# Sheet1.net
KiCad netlist of a schematic drawn in Altium Designer
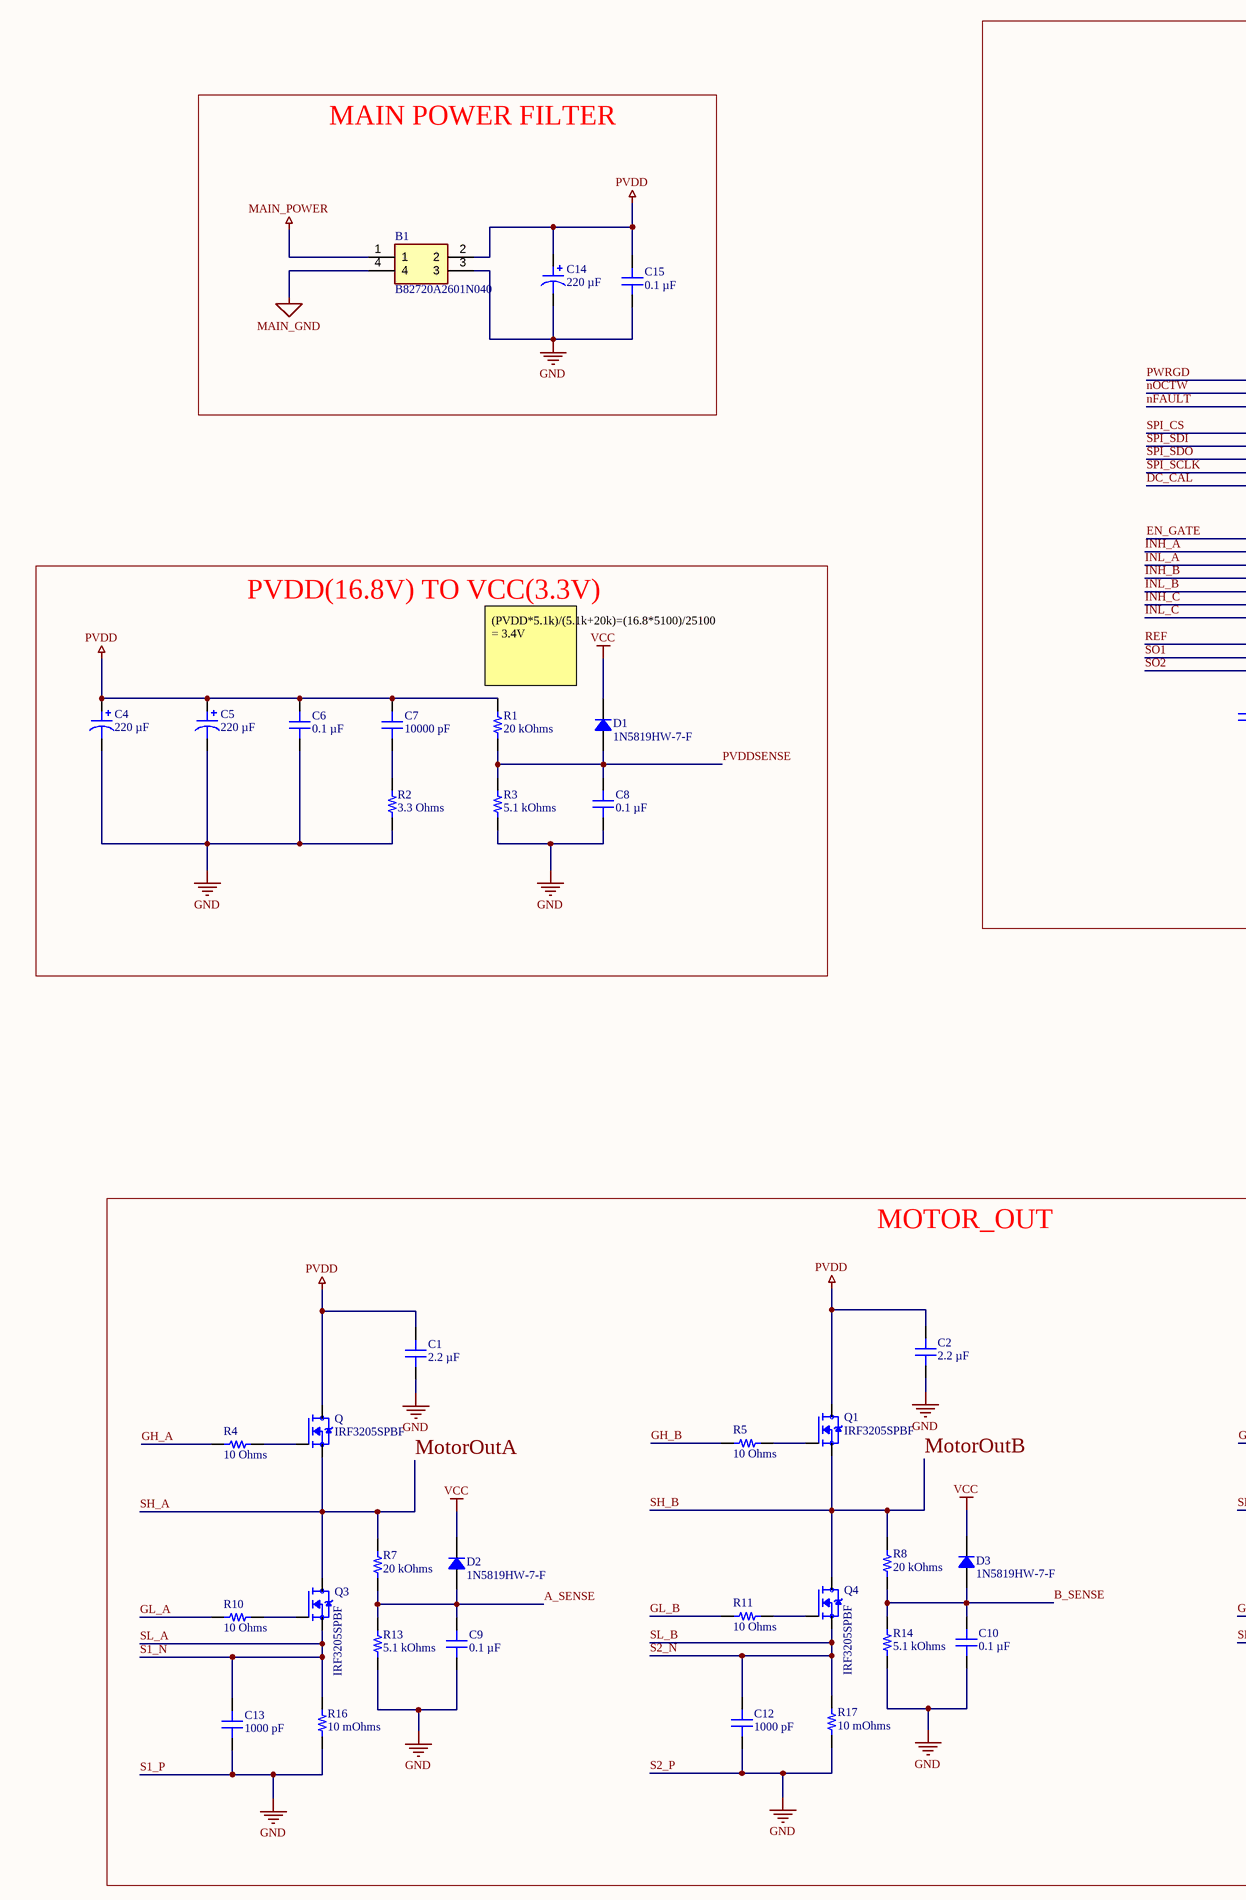
[diagram p0: Sheet1.SchDoc, left]
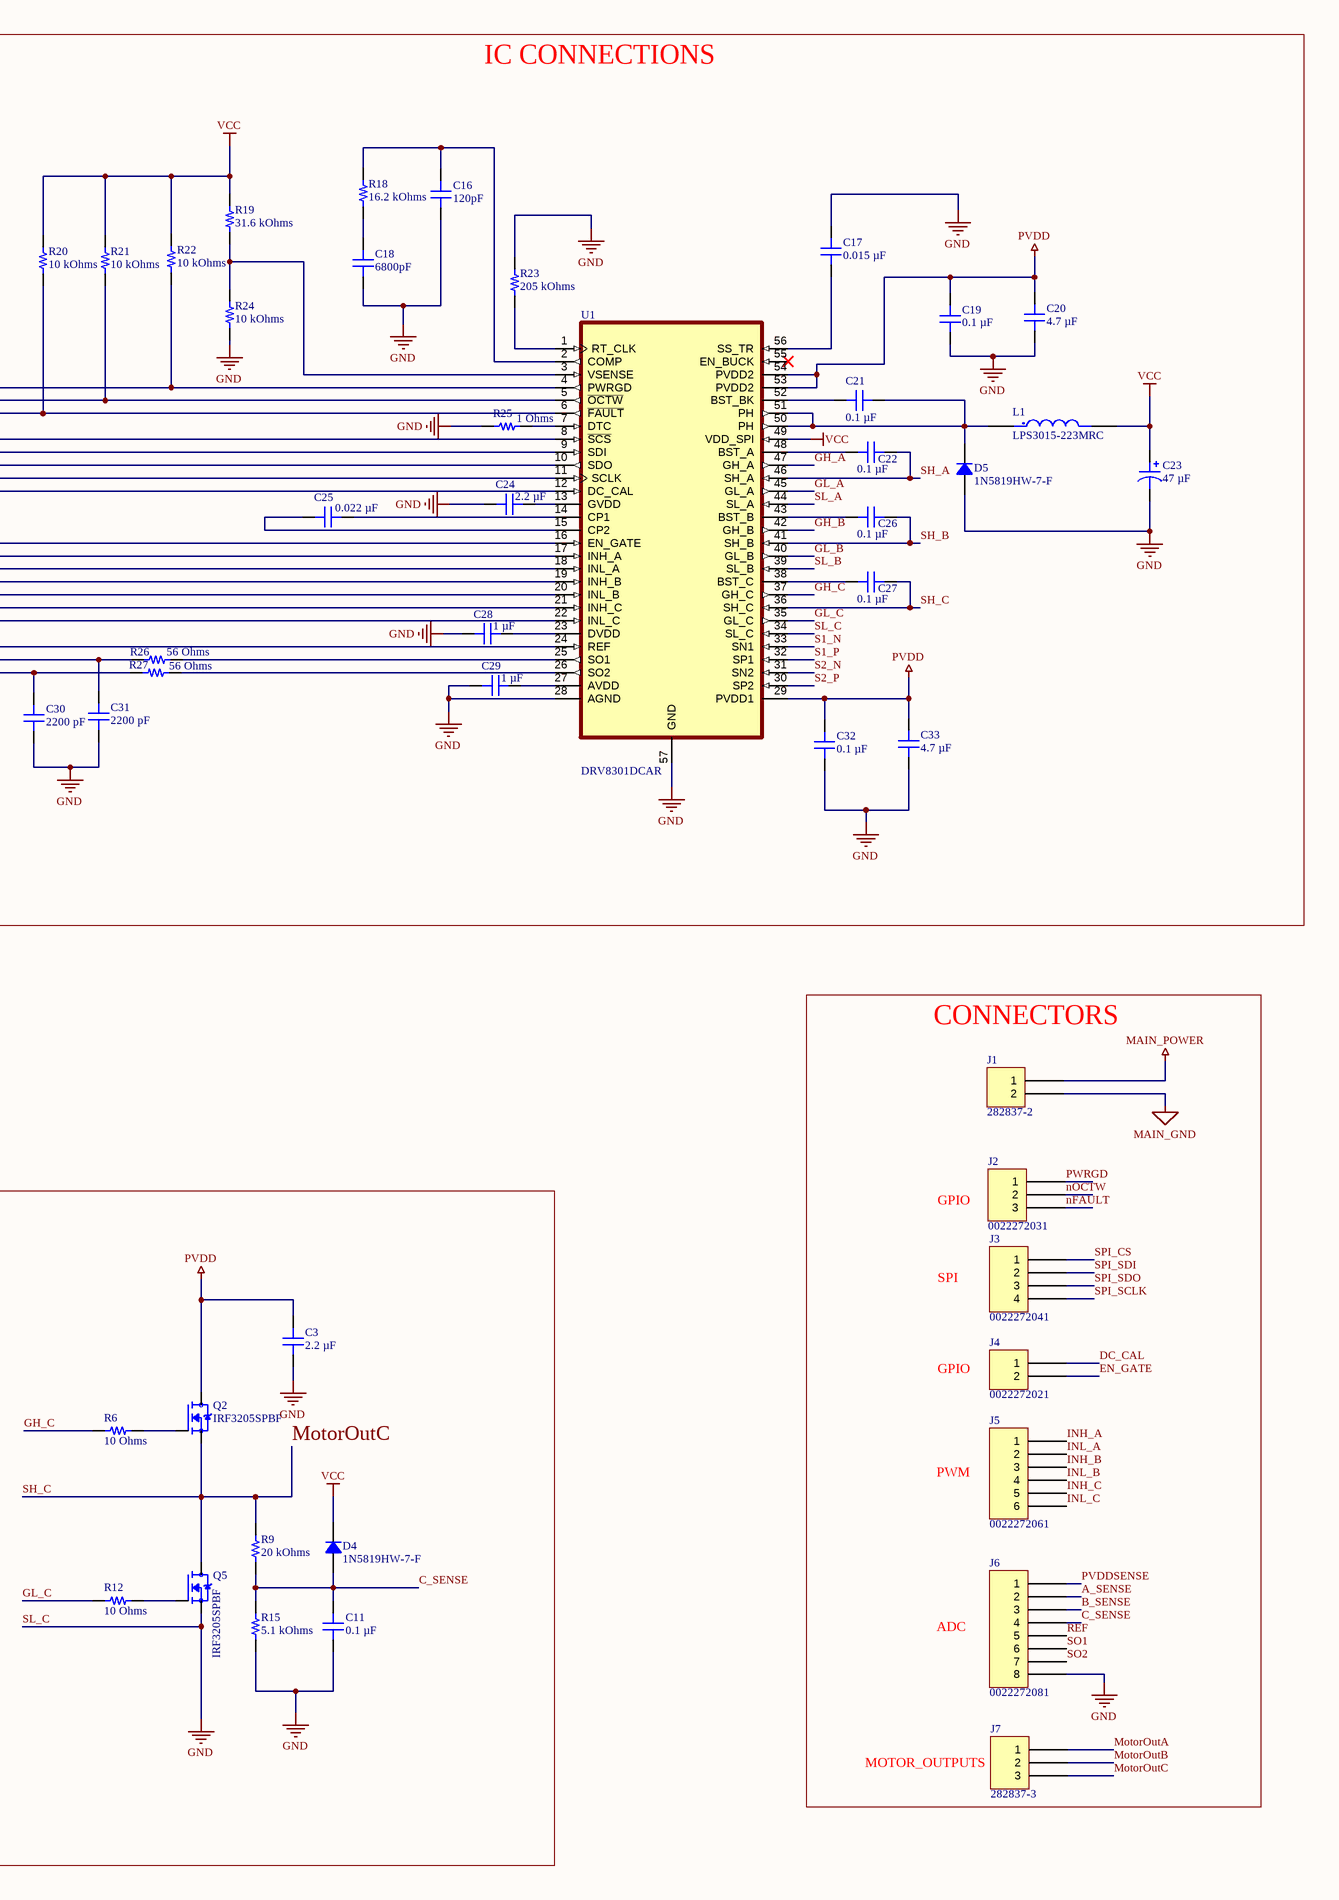
[diagram p1: Sheet1.SchDoc, right]

(export (version "E")
  (design (tool "Eeschema 10.0.6"))
  (components
    (comp (ref "B1")
      (value "B82720A2601N040")
      (footprint "B82720A2601N040")
      (description "Power Line Chokes, L=4.4mH  Rated current=0.6A, LxWxT:14.2mmx14.2mmx9.6mm")
      (fields (field (name "MOUSER PART NUMBER") "871-B82720A2601N40"))
      (libsource (lib "MyAltLib") (part "B82720A2601N040"))
    )
    (comp (ref "C1")
      (value "2.2 µF")
      (footprint "CAP 0805_2012")
      (description "CAP CER 2.2UF 50V X5R 0805")
      (fields
        (field (name "PART NUMBER") "CL21A225KB9LNNC")
        (field (name "CAPACITANCE") "2.2 µF")
        (field (name "MANUFACTURER") "Samsung Electro-Mechanics")
      )
      (libsource (lib "Celestial Altium Library - altium_library") (part "Capacitor"))
    )
    (comp (ref "C2")
      (value "2.2 µF")
      (footprint "CAP 0805_2012")
      (description "CAP CER 2.2UF 50V X5R 0805")
      (fields
        (field (name "PART NUMBER") "CL21A225KB9LNNC")
        (field (name "CAPACITANCE") "2.2 µF")
        (field (name "MANUFACTURER") "Samsung Electro-Mechanics")
      )
      (libsource (lib "Celestial Altium Library - altium_library") (part "Capacitor"))
    )
    (comp (ref "C3")
      (value "2.2 µF")
      (footprint "CAP 0805_2012")
      (description "CAP CER 2.2UF 50V X5R 0805")
      (fields
        (field (name "PART NUMBER") "CL21A225KB9LNNC")
        (field (name "CAPACITANCE") "2.2 µF")
        (field (name "MANUFACTURER") "Samsung Electro-Mechanics")
      )
      (libsource (lib "Celestial Altium Library - altium_library") (part "Capacitor"))
    )
    (comp (ref "C4")
      (value "220 µF")
      (footprint "CAP ALSMD 8.3MM H10.5MM")
      (description "CAP ALUM 220UF 20% 35V SMD")
      (fields
        (field (name "PART NUMBER") "EEE-FK1V221AL")
        (field (name "MANUFACTURER") "Panasonic Electronic Components")
      )
      (libsource (lib "Celestial Altium Library - altium_library") (part "Polarised Capacitor"))
    )
    (comp (ref "C5")
      (value "220 µF")
      (footprint "CAP ALSMD 8.3MM H10.5MM")
      (description "CAP ALUM 220UF 20% 35V SMD")
      (fields
        (field (name "PART NUMBER") "EEE-FK1V221AL")
        (field (name "MANUFACTURER") "Panasonic Electronic Components")
      )
      (libsource (lib "Celestial Altium Library - altium_library") (part "Polarised Capacitor"))
    )
    (comp (ref "C6")
      (value "0.1 µF")
      (footprint "CAP 0805_2012")
      (description "CAP CER 0.1UF 50V X7R 0805")
      (fields
        (field (name "PART NUMBER") "CC0805MRX7R9BB104")
        (field (name "CAPACITANCE") "0.1 µF")
        (field (name "MANUFACTURER") "Yageo")
      )
      (libsource (lib "Celestial Altium Library - altium_library") (part "Capacitor"))
    )
    (comp (ref "C7")
      (value "10000 pF")
      (footprint "CAP 0805_2012")
      (description "CAP CER 0805 10NF 50V X7R 10%")
      (fields
        (field (name "PART NUMBER") "C0805C103K5RECAUTO")
        (field (name "CAPACITANCE") "10000 pF")
        (field (name "MANUFACTURER") "KEMET")
      )
      (libsource (lib "Celestial Altium Library - altium_library") (part "Capacitor"))
    )
    (comp (ref "C8")
      (value "0.1 µF")
      (footprint "CAP 0805_2012")
      (description "CAP CER 0.1UF 50V X7R 0805")
      (fields
        (field (name "PART NUMBER") "CC0805MRX7R9BB104")
        (field (name "CAPACITANCE") "0.1 µF")
        (field (name "MANUFACTURER") "Yageo")
      )
      (libsource (lib "Celestial Altium Library - altium_library") (part "Capacitor"))
    )
    (comp (ref "C9")
      (value "0.1 µF")
      (footprint "CAP 0805_2012")
      (description "CAP CER 0.1UF 50V X7R 0805")
      (fields
        (field (name "PART NUMBER") "CC0805MRX7R9BB104")
        (field (name "CAPACITANCE") "0.1 µF")
        (field (name "MANUFACTURER") "Yageo")
      )
      (libsource (lib "Celestial Altium Library - altium_library") (part "Capacitor"))
    )
    (comp (ref "C10")
      (value "0.1 µF")
      (footprint "CAP 0805_2012")
      (description "CAP CER 0.1UF 50V X7R 0805")
      (fields
        (field (name "PART NUMBER") "CC0805MRX7R9BB104")
        (field (name "CAPACITANCE") "0.1 µF")
        (field (name "MANUFACTURER") "Yageo")
      )
      (libsource (lib "Celestial Altium Library - altium_library") (part "Capacitor"))
    )
    (comp (ref "C11")
      (value "0.1 µF")
      (footprint "CAP 0805_2012")
      (description "CAP CER 0.1UF 50V X7R 0805")
      (fields
        (field (name "PART NUMBER") "CC0805MRX7R9BB104")
        (field (name "CAPACITANCE") "0.1 µF")
        (field (name "MANUFACTURER") "Yageo")
      )
      (libsource (lib "Celestial Altium Library - altium_library") (part "Capacitor"))
    )
    (comp (ref "C12")
      (value "1000 pF")
      (footprint "CAP 0805_2012")
      (description "CAP CER 1000PF 50V C0G/NP0 0805")
      (fields
        (field (name "PART NUMBER") "500R15N102JV4T")
        (field (name "CAPACITANCE") "1000 pF")
        (field (name "MANUFACTURER") "Johanson Dielectrics Inc.")
      )
      (libsource (lib "Celestial Altium Library - altium_library") (part "Capacitor"))
    )
    (comp (ref "C13")
      (value "1000 pF")
      (footprint "CAP 0805_2012")
      (description "CAP CER 1000PF 50V C0G/NP0 0805")
      (fields
        (field (name "PART NUMBER") "500R15N102JV4T")
        (field (name "CAPACITANCE") "1000 pF")
        (field (name "MANUFACTURER") "Johanson Dielectrics Inc.")
      )
      (libsource (lib "Celestial Altium Library - altium_library") (part "Capacitor"))
    )
    (comp (ref "C14")
      (value "220 µF")
      (footprint "CAP ALSMD 8.3MM H10.5MM")
      (description "CAP ALUM 220UF 20% 35V SMD")
      (fields
        (field (name "PART NUMBER") "EEE-FK1V221AL")
        (field (name "MANUFACTURER") "Panasonic Electronic Components")
      )
      (libsource (lib "Celestial Altium Library - altium_library") (part "Polarised Capacitor"))
    )
    (comp (ref "C15")
      (value "0.1 µF")
      (footprint "CAP 0805_2012")
      (description "CAP CER 0.1UF 50V X7R 0805")
      (fields
        (field (name "PART NUMBER") "CC0805MRX7R9BB104")
        (field (name "CAPACITANCE") "0.1 µF")
        (field (name "MANUFACTURER") "Yageo")
      )
      (libsource (lib "Celestial Altium Library - altium_library") (part "Capacitor"))
    )
    (comp (ref "C16")
      (value "120pF")
      (footprint "CAP 0805_2012")
      (description "CAP CER 120PF 50V C0G/NP0 0805")
      (fields
        (field (name "PART NUMBER") "08055A121JAT2A")
        (field (name "CAPACITANCE") "120pF")
        (field (name "MANUFACTURER") "AVX Corporation")
      )
      (libsource (lib "Celestial Altium Library - altium_library") (part "Capacitor"))
    )
    (comp (ref "C17")
      (value "0.015 µF")
      (footprint "CAP 0805_2012")
      (description "CAP CER 0.015UF 50V X7R 0805")
      (fields
        (field (name "PART NUMBER") "C0805C153K5RACAUTO")
        (field (name "CAPACITANCE") "0.015 µF")
        (field (name "MANUFACTURER") "KEMET")
      )
      (libsource (lib "Celestial Altium Library - altium_library") (part "Capacitor"))
    )
    (comp (ref "C18")
      (value "6800pF")
      (footprint "CAP 0805_2012")
      (description "CAP CER 6800PF 50V X7R 0805")
      (fields
        (field (name "PART NUMBER") "08055C682KAT2A")
        (field (name "CAPACITANCE") "6800pF")
        (field (name "MANUFACTURER") "AVX Corporation")
      )
      (libsource (lib "Celestial Altium Library - altium_library") (part "Capacitor"))
    )
    (comp (ref "C19")
      (value "0.1 µF")
      (footprint "CAP 0805_2012")
      (description "CAP CER 0.1UF 50V X7R 0805")
      (fields
        (field (name "PART NUMBER") "CC0805MRX7R9BB104")
        (field (name "CAPACITANCE") "0.1 µF")
        (field (name "MANUFACTURER") "Yageo")
      )
      (libsource (lib "Celestial Altium Library - altium_library") (part "Capacitor"))
    )
    (comp (ref "C20")
      (value "4.7 µF")
      (footprint "CAP 0805_2012")
      (description "CAP CER 4.7UF 50V X5R 0805")
      (fields
        (field (name "PART NUMBER") "CL21A475KBQNNNE")
        (field (name "CAPACITANCE") "4.7 µF")
        (field (name "MANUFACTURER") "Samsung Electro-Mechanics")
      )
      (libsource (lib "Celestial Altium Library - altium_library") (part "Capacitor"))
    )
    (comp (ref "C21")
      (value "0.1 µF")
      (footprint "CAP 0805_2012")
      (description "CAP CER 0.1UF 50V X7R 0805")
      (fields
        (field (name "PART NUMBER") "CC0805MRX7R9BB104")
        (field (name "CAPACITANCE") "0.1 µF")
        (field (name "MANUFACTURER") "Yageo")
      )
      (libsource (lib "Celestial Altium Library - altium_library") (part "Capacitor"))
    )
    (comp (ref "C22")
      (value "0.1 µF")
      (footprint "CAP 0805_2012")
      (description "CAP CER 0.1UF 50V X7R 0805")
      (fields
        (field (name "PART NUMBER") "CC0805MRX7R9BB104")
        (field (name "CAPACITANCE") "0.1 µF")
        (field (name "MANUFACTURER") "Yageo")
      )
      (libsource (lib "Celestial Altium Library - altium_library") (part "Capacitor"))
    )
    (comp (ref "C23")
      (value "47 µF")
      (footprint "CAP ALSMD 8.3MM H10.5MM")
      (description "CAP ALUM 47UF 20% 63V SMD")
      (fields
        (field (name "PART NUMBER") "EEE-FK1J470P")
        (field (name "MANUFACTURER") "Panasonic Electronic Components")
      )
      (libsource (lib "Celestial Altium Library - altium_library") (part "Polarised Capacitor"))
    )
    (comp (ref "C24")
      (value "2.2 µF")
      (footprint "CAP 0805_2012")
      (description "CAP CER 2.2UF 50V X5R 0805")
      (fields
        (field (name "PART NUMBER") "CL21A225KB9LNNC")
        (field (name "CAPACITANCE") "2.2 µF")
        (field (name "MANUFACTURER") "Samsung Electro-Mechanics")
      )
      (libsource (lib "Celestial Altium Library - altium_library") (part "Capacitor"))
    )
    (comp (ref "C25")
      (value "0.022 µF")
      (footprint "CAP 0805_2012")
      (description "CAP CER 0.022UF 50V X7R 0805")
      (fields
        (field (name "PART NUMBER") "C0805X223K5RECAUTO")
        (field (name "CAPACITANCE") "0.022 µF")
        (field (name "MANUFACTURER") "KEMET")
      )
      (libsource (lib "Celestial Altium Library - altium_library") (part "Capacitor"))
    )
    (comp (ref "C26")
      (value "0.1 µF")
      (footprint "CAP 0805_2012")
      (description "CAP CER 0.1UF 50V X7R 0805")
      (fields
        (field (name "PART NUMBER") "CC0805MRX7R9BB104")
        (field (name "CAPACITANCE") "0.1 µF")
        (field (name "MANUFACTURER") "Yageo")
      )
      (libsource (lib "Celestial Altium Library - altium_library") (part "Capacitor"))
    )
    (comp (ref "C27")
      (value "0.1 µF")
      (footprint "CAP 0805_2012")
      (description "CAP CER 0.1UF 50V X7R 0805")
      (fields
        (field (name "PART NUMBER") "CC0805MRX7R9BB104")
        (field (name "CAPACITANCE") "0.1 µF")
        (field (name "MANUFACTURER") "Yageo")
      )
      (libsource (lib "Celestial Altium Library - altium_library") (part "Capacitor"))
    )
    (comp (ref "C28")
      (value "1 µF")
      (footprint "CAP 0805_2012")
      (description "CAP CER 1UF 50V X7R 0805")
      (fields
        (field (name "PART NUMBER") "GCJ21BR71H105KA01L")
        (field (name "CAPACITANCE") "1 µF")
        (field (name "MANUFACTURER") "Murata Electronics")
      )
      (libsource (lib "Celestial Altium Library - altium_library") (part "Capacitor"))
    )
    (comp (ref "C29")
      (value "1 µF")
      (footprint "CAP 0805_2012")
      (description "CAP CER 1UF 50V X7R 0805")
      (fields
        (field (name "PART NUMBER") "GCJ21BR71H105KA01L")
        (field (name "CAPACITANCE") "1 µF")
        (field (name "MANUFACTURER") "Murata Electronics")
      )
      (libsource (lib "Celestial Altium Library - altium_library") (part "Capacitor"))
    )
    (comp (ref "C30")
      (value "2200 pF")
      (footprint "CAP 0805_2012")
      (description "CAP CER 2200PF 200V X7R 0805")
      (fields
        (field (name "PART NUMBER") "CC0805KRX7RABB222")
        (field (name "CAPACITANCE") "2200 pF")
        (field (name "MANUFACTURER") "Yageo")
      )
      (libsource (lib "Celestial Altium Library - altium_library") (part "Capacitor"))
    )
    (comp (ref "C31")
      (value "2200 pF")
      (footprint "CAP 0805_2012")
      (description "CAP CER 2200PF 200V X7R 0805")
      (fields
        (field (name "PART NUMBER") "CC0805KRX7RABB222")
        (field (name "CAPACITANCE") "2200 pF")
        (field (name "MANUFACTURER") "Yageo")
      )
      (libsource (lib "Celestial Altium Library - altium_library") (part "Capacitor"))
    )
    (comp (ref "C32")
      (value "0.1 µF")
      (footprint "CAP 0805_2012")
      (description "CAP CER 0.1UF 50V X7R 0805")
      (fields
        (field (name "PART NUMBER") "CC0805MRX7R9BB104")
        (field (name "CAPACITANCE") "0.1 µF")
        (field (name "MANUFACTURER") "Yageo")
      )
      (libsource (lib "Celestial Altium Library - altium_library") (part "Capacitor"))
    )
    (comp (ref "C33")
      (value "4.7 µF")
      (footprint "CAP 0805_2012")
      (description "CAP CER 4.7UF 50V X5R 0805")
      (fields
        (field (name "PART NUMBER") "CL21A475KBQNNNE")
        (field (name "CAPACITANCE") "4.7 µF")
        (field (name "MANUFACTURER") "Samsung Electro-Mechanics")
      )
      (libsource (lib "Celestial Altium Library - altium_library") (part "Capacitor"))
    )
    (comp (ref "D1")
      (value "1N5819HW-7-F")
      (footprint "SOD-123")
      (description "DIODE SCHOTTKY 40V 1A SOD123")
      (fields (field (name "MANUFACTURER") "Diodes Incorporated"))
      (libsource (lib "Celestial Altium Library - altium_library") (part "Diode"))
    )
    (comp (ref "D2")
      (value "1N5819HW-7-F")
      (footprint "SOD-123")
      (description "DIODE SCHOTTKY 40V 1A SOD123")
      (fields (field (name "MANUFACTURER") "Diodes Incorporated"))
      (libsource (lib "Celestial Altium Library - altium_library") (part "Diode"))
    )
    (comp (ref "D3")
      (value "1N5819HW-7-F")
      (footprint "SOD-123")
      (description "DIODE SCHOTTKY 40V 1A SOD123")
      (fields (field (name "MANUFACTURER") "Diodes Incorporated"))
      (libsource (lib "Celestial Altium Library - altium_library") (part "Diode"))
    )
    (comp (ref "D4")
      (value "1N5819HW-7-F")
      (footprint "SOD-123")
      (description "DIODE SCHOTTKY 40V 1A SOD123")
      (fields (field (name "MANUFACTURER") "Diodes Incorporated"))
      (libsource (lib "Celestial Altium Library - altium_library") (part "Diode"))
    )
    (comp (ref "D5")
      (value "1N5819HW-7-F")
      (footprint "SOD-123")
      (description "DIODE SCHOTTKY 40V 1A SOD123")
      (fields (field (name "MANUFACTURER") "Diodes Incorporated"))
      (libsource (lib "Celestial Altium Library - altium_library") (part "Diode"))
    )
    (comp (ref "J1")
      (value "282837-2")
      (footprint "TE 282837-2")
      (description "TERM BLK 2P SIDE ENT 5.08MM PCB")
      (fields (field (name "MANUFACTURER") "TE Connectivity AMP Connectors") (field (name "VOLTAGE") "300 V"))
      (libsource (lib "Celestial Altium Library - altium_library") (part "2 Pin"))
    )
    (comp (ref "J2")
      (value "0022272031")
      (footprint "MOLEX KK 0022272031")
      (description "CONN HEADER VERT 3POS 2.54MM")
      (fields (field (name "MANUFACTURER") "Molex"))
      (libsource (lib "Celestial Altium Library - altium_library") (part "3 Pin"))
    )
    (comp (ref "J3")
      (value "0022272041")
      (footprint "MOLEX KK 0022272041")
      (description "CONN HEADER VERT 4POS 2.54MM")
      (fields (field (name "MANUFACTURER") "Molex"))
      (libsource (lib "Celestial Altium Library - altium_library") (part "4 Pin"))
    )
    (comp (ref "J4")
      (value "0022272021")
      (footprint "MOLEX KK 0022272021")
      (description "CONN HEADER VERT 2POS 2.54MM")
      (fields (field (name "MANUFACTURER") "Molex"))
      (libsource (lib "Celestial Altium Library - altium_library") (part "2 Pin"))
    )
    (comp (ref "J5")
      (value "0022272061")
      (footprint "MOLEX KK 0022272061")
      (description "CONN HEADER VERT 6POS 2.54MM")
      (fields (field (name "MANUFACTURER") "Molex"))
      (libsource (lib "Celestial Altium Library - altium_library") (part "6 Pin"))
    )
    (comp (ref "J6")
      (value "0022272081")
      (footprint "MOLEX KK 0022272081")
      (description "CONN HEADER VERT 8POS 2.54MM")
      (fields (field (name "MANUFACTURER") "Molex"))
      (libsource (lib "Celestial Altium Library - altium_library") (part "8 Pin"))
    )
    (comp (ref "J7")
      (value "282837-3")
      (footprint "TE 282837-3")
      (description "TERM BLK 3P SIDE ENT 5.08MM PCB")
      (fields (field (name "MANUFACTURER") "TE Connectivity AMP Connectors") (field (name "VOLTAGE") "300 V"))
      (libsource (lib "Celestial Altium Library - altium_library") (part "3 Pin"))
    )
    (comp (ref "L1")
      (value "LPS3015-223MRC")
      (footprint "IND_LPS3015-223MRC")
      (description "22 ÂµH Shielded - Inductor 570 mA 825mOhm Max Nonstandard -")
      (fields (field (name "MF") "Coilcraft"))
      (libsource (lib "MyAltLib") (part "LPS3015-223MRC"))
    )
    (comp (ref "Q")
      (value "IRF3205SPBF")
      (footprint "D2PAK-3 (TO-263-3)")
      (fields (field (name "MF") "Infineon Technologies"))
      (libsource (lib "MyAltLib") (part "IRF3205SPBF"))
    )
    (comp (ref "Q1")
      (value "IRF3205SPBF")
      (footprint "D2PAK-3 (TO-263-3)")
      (fields (field (name "MF") "Infineon Technologies"))
      (libsource (lib "MyAltLib") (part "IRF3205SPBF"))
    )
    (comp (ref "Q2")
      (value "IRF3205SPBF")
      (footprint "D2PAK-3 (TO-263-3)")
      (fields (field (name "MF") "Infineon Technologies"))
      (libsource (lib "MyAltLib") (part "IRF3205SPBF"))
    )
    (comp (ref "Q3")
      (value "IRF3205SPBF")
      (footprint "D2PAK-3 (TO-263-3)")
      (fields (field (name "MF") "Infineon Technologies"))
      (libsource (lib "MyAltLib") (part "IRF3205SPBF"))
    )
    (comp (ref "Q4")
      (value "IRF3205SPBF")
      (footprint "D2PAK-3 (TO-263-3)")
      (fields (field (name "MF") "Infineon Technologies"))
      (libsource (lib "MyAltLib") (part "IRF3205SPBF"))
    )
    (comp (ref "Q5")
      (value "IRF3205SPBF")
      (footprint "D2PAK-3 (TO-263-3)")
      (fields (field (name "MF") "Infineon Technologies"))
      (libsource (lib "MyAltLib") (part "IRF3205SPBF"))
    )
    (comp (ref "R1")
      (value "20 kOhms")
      (footprint "RES 0805_2012")
      (description "RES 20K OHM 0.1% 1/10W 0805")
      (fields
        (field (name "PART NUMBER") "RNCS0805BKE20K0")
        (field (name "MANUFACTURER") "Stackpole Electronics Inc")
      )
      (libsource (lib "Celestial Altium Library - altium_library") (part "Resistor"))
    )
    (comp (ref "R2")
      (value "3.3 Ohms")
      (footprint "RES 0805_2012")
      (description "RES SMD 3.3 OHM 1% 1/2W 0805")
      (fields (field (name "PART NUMBER") "CRCW08053R30FKEAHP") (field (name "MANUFACTURER") "Vishay Dale"))
      (libsource (lib "Celestial Altium Library - altium_library") (part "Resistor"))
    )
    (comp (ref "R3")
      (value "5.1 kOhms")
      (footprint "RES 0805_2012")
      (description "RES SMD 5.1K OHM 0.5% 1/8W 0805")
      (fields
        (field (name "PART NUMBER") "ERA-6AED512V")
        (field (name "MANUFACTURER") "Panasonic Electronic Components")
      )
      (libsource (lib "Celestial Altium Library - altium_library") (part "Resistor"))
    )
    (comp (ref "R4")
      (value "10 Ohms")
      (footprint "RES 0805_2012")
      (description "RES 10 OHM 0.1% 1/10W 0805")
      (fields
        (field (name "PART NUMBER") "RNCS0805BKE10R0")
        (field (name "MANUFACTURER") "Stackpole Electronics Inc")
      )
      (libsource (lib "Celestial Altium Library - altium_library") (part "Resistor"))
    )
    (comp (ref "R5")
      (value "10 Ohms")
      (footprint "RES 0805_2012")
      (description "RES 10 OHM 0.1% 1/10W 0805")
      (fields
        (field (name "PART NUMBER") "RNCS0805BKE10R0")
        (field (name "MANUFACTURER") "Stackpole Electronics Inc")
      )
      (libsource (lib "Celestial Altium Library - altium_library") (part "Resistor"))
    )
    (comp (ref "R6")
      (value "10 Ohms")
      (footprint "RES 0805_2012")
      (description "RES 10 OHM 0.1% 1/10W 0805")
      (fields
        (field (name "PART NUMBER") "RNCS0805BKE10R0")
        (field (name "MANUFACTURER") "Stackpole Electronics Inc")
      )
      (libsource (lib "Celestial Altium Library - altium_library") (part "Resistor"))
    )
    (comp (ref "R7")
      (value "20 kOhms")
      (footprint "RES 0805_2012")
      (description "RES 20K OHM 0.1% 1/10W 0805")
      (fields
        (field (name "PART NUMBER") "RNCS0805BKE20K0")
        (field (name "MANUFACTURER") "Stackpole Electronics Inc")
      )
      (libsource (lib "Celestial Altium Library - altium_library") (part "Resistor"))
    )
    (comp (ref "R8")
      (value "20 kOhms")
      (footprint "RES 0805_2012")
      (description "RES 20K OHM 0.1% 1/10W 0805")
      (fields
        (field (name "PART NUMBER") "RNCS0805BKE20K0")
        (field (name "MANUFACTURER") "Stackpole Electronics Inc")
      )
      (libsource (lib "Celestial Altium Library - altium_library") (part "Resistor"))
    )
    (comp (ref "R9")
      (value "20 kOhms")
      (footprint "RES 0805_2012")
      (description "RES 20K OHM 0.1% 1/10W 0805")
      (fields
        (field (name "PART NUMBER") "RNCS0805BKE20K0")
        (field (name "MANUFACTURER") "Stackpole Electronics Inc")
      )
      (libsource (lib "Celestial Altium Library - altium_library") (part "Resistor"))
    )
    (comp (ref "R10")
      (value "10 Ohms")
      (footprint "RES 0805_2012")
      (description "RES 10 OHM 0.1% 1/10W 0805")
      (fields
        (field (name "PART NUMBER") "RNCS0805BKE10R0")
        (field (name "MANUFACTURER") "Stackpole Electronics Inc")
      )
      (libsource (lib "Celestial Altium Library - altium_library") (part "Resistor"))
    )
    (comp (ref "R11")
      (value "10 Ohms")
      (footprint "RES 0805_2012")
      (description "RES 10 OHM 0.1% 1/10W 0805")
      (fields
        (field (name "PART NUMBER") "RNCS0805BKE10R0")
        (field (name "MANUFACTURER") "Stackpole Electronics Inc")
      )
      (libsource (lib "Celestial Altium Library - altium_library") (part "Resistor"))
    )
    (comp (ref "R12")
      (value "10 Ohms")
      (footprint "RES 0805_2012")
      (description "RES 10 OHM 0.1% 1/10W 0805")
      (fields
        (field (name "PART NUMBER") "RNCS0805BKE10R0")
        (field (name "MANUFACTURER") "Stackpole Electronics Inc")
      )
      (libsource (lib "Celestial Altium Library - altium_library") (part "Resistor"))
    )
    (comp (ref "R13")
      (value "5.1 kOhms")
      (footprint "RES 0805_2012")
      (description "RES SMD 5.1K OHM 0.5% 1/8W 0805")
      (fields
        (field (name "PART NUMBER") "ERA-6AED512V")
        (field (name "MANUFACTURER") "Panasonic Electronic Components")
      )
      (libsource (lib "Celestial Altium Library - altium_library") (part "Resistor"))
    )
    (comp (ref "R14")
      (value "5.1 kOhms")
      (footprint "RES 0805_2012")
      (description "RES SMD 5.1K OHM 0.5% 1/8W 0805")
      (fields
        (field (name "PART NUMBER") "ERA-6AED512V")
        (field (name "MANUFACTURER") "Panasonic Electronic Components")
      )
      (libsource (lib "Celestial Altium Library - altium_library") (part "Resistor"))
    )
    (comp (ref "R15")
      (value "5.1 kOhms")
      (footprint "RES 0805_2012")
      (description "RES SMD 5.1K OHM 0.5% 1/8W 0805")
      (fields
        (field (name "PART NUMBER") "ERA-6AED512V")
        (field (name "MANUFACTURER") "Panasonic Electronic Components")
      )
      (libsource (lib "Celestial Altium Library - altium_library") (part "Resistor"))
    )
    (comp (ref "R16")
      (value "10 mOhms")
      (footprint "RES 0805_2012")
      (description "RES 0.01 OHM 5% 1/2W 0805")
      (fields (field (name "PART NUMBER") "PMR10EZPJU10L") (field (name "MANUFACTURER") "Rohm Semiconductor"))
      (libsource (lib "Celestial Altium Library - altium_library") (part "Resistor"))
    )
    (comp (ref "R17")
      (value "10 mOhms")
      (footprint "RES 0805_2012")
      (description "RES 0.01 OHM 5% 1/2W 0805")
      (fields (field (name "PART NUMBER") "PMR10EZPJU10L") (field (name "MANUFACTURER") "Rohm Semiconductor"))
      (libsource (lib "Celestial Altium Library - altium_library") (part "Resistor"))
    )
    (comp (ref "R18")
      (value "16.2 kOhms")
      (footprint "RES 0805_2012")
      (description "RA73F 2A 16K2 0.1% 5K RL")
      (fields
        (field (name "PART NUMBER") "RA73F2A16K2BTD")
        (field (name "MANUFACTURER") "TE Connectivity Passive Product")
      )
      (libsource (lib "Celestial Altium Library - altium_library") (part "Resistor"))
    )
    (comp (ref "R19")
      (value "31.6 kOhms")
      (footprint "RES 0805_2012")
      (description "RES SMD 31.6KOHM 0.1% 1/10W 0805")
      (fields
        (field (name "PART NUMBER") "RN73C2A31K6BTDF")
        (field (name "MANUFACTURER") "TE Connectivity Passive Product")
      )
      (libsource (lib "Celestial Altium Library - altium_library") (part "Resistor"))
    )
    (comp (ref "R20")
      (value "10 kOhms")
      (footprint "RES 0805_2012")
      (description "RES 10K OHM 0.1% 1/10W 0805")
      (fields
        (field (name "PART NUMBER") "RNCS0805BKE10K0")
        (field (name "MANUFACTURER") "Stackpole Electronics Inc")
      )
      (libsource (lib "Celestial Altium Library - altium_library") (part "Resistor"))
    )
    (comp (ref "R21")
      (value "10 kOhms")
      (footprint "RES 0805_2012")
      (description "RES 10K OHM 0.1% 1/10W 0805")
      (fields
        (field (name "PART NUMBER") "RNCS0805BKE10K0")
        (field (name "MANUFACTURER") "Stackpole Electronics Inc")
      )
      (libsource (lib "Celestial Altium Library - altium_library") (part "Resistor"))
    )
    (comp (ref "R22")
      (value "10 kOhms")
      (footprint "RES 0805_2012")
      (description "RES 10K OHM 0.1% 1/10W 0805")
      (fields
        (field (name "PART NUMBER") "RNCS0805BKE10K0")
        (field (name "MANUFACTURER") "Stackpole Electronics Inc")
      )
      (libsource (lib "Celestial Altium Library - altium_library") (part "Resistor"))
    )
    (comp (ref "R23")
      (value "205 kOhms")
      (footprint "RES 0805_2012")
      (description "RES SMD 205K OHM 1% 1/8W 0805")
      (fields (field (name "PART NUMBER") "CRCW0805205KFKEA") (field (name "MANUFACTURER") "Vishay Dale"))
      (libsource (lib "Celestial Altium Library - altium_library") (part "Resistor"))
    )
    (comp (ref "R24")
      (value "10 kOhms")
      (footprint "RES 0805_2012")
      (description "RES 10K OHM 0.1% 1/10W 0805")
      (fields
        (field (name "PART NUMBER") "RNCS0805BKE10K0")
        (field (name "MANUFACTURER") "Stackpole Electronics Inc")
      )
      (libsource (lib "Celestial Altium Library - altium_library") (part "Resistor"))
    )
    (comp (ref "R25")
      (value "1 Ohms")
      (footprint "RES 0805_2012")
      (description "RES SMD 1 OHM 1% 1/3W 0805")
      (fields (field (name "PART NUMBER") "RL1220S-1R0-F") (field (name "MANUFACTURER") "Susumu"))
      (libsource (lib "Celestial Altium Library - altium_library") (part "Resistor"))
    )
    (comp (ref "R26")
      (value "56 Ohms")
      (footprint "RES 0805_2012")
      (description "RES SMD 56 OHM 0.1% 1/8W 0805")
      (fields
        (field (name "PART NUMBER") "ERA-6AEB560V")
        (field (name "MANUFACTURER") "Panasonic Electronic Components")
      )
      (libsource (lib "Celestial Altium Library - altium_library") (part "Resistor"))
    )
    (comp (ref "R27")
      (value "56 Ohms")
      (footprint "RES 0805_2012")
      (description "RES SMD 56 OHM 0.1% 1/8W 0805")
      (fields
        (field (name "PART NUMBER") "ERA-6AEB560V")
        (field (name "MANUFACTURER") "Panasonic Electronic Components")
      )
      (libsource (lib "Celestial Altium Library - altium_library") (part "Resistor"))
    )
    (comp (ref "U1")
      (value "DRV8301DCAR")
      (footprint "HTSSOP-56")
      (description "GATE DRIVER FOR BRUSHLESS DC  MOTORS")
      (fields (field (name "DIGI-KEY_PART_NUMBER") "296-29433-1-ND") (field (name "MF") "Texas Instruments"))
      (libsource (lib "MyAltLib") (part "DRV8301DCAR"))
    )
  )
  (nets
    (net (code "1") (name "/A_SENSE") (class "Default")
      (node (ref "C9") (pin "2") (pinfunction "2_2") (pintype "passive"))
      (node (ref "D2") (pin "1") (pinfunction "1_1") (pintype "passive"))
      (node (ref "J6") (pin "2") (pinfunction "2_2") (pintype "passive"))
      (node (ref "R13") (pin "2") (pinfunction "2_2") (pintype "passive"))
      (node (ref "R7") (pin "1") (pinfunction "1_1") (pintype "passive"))
    )
    (net (code "2") (name "/B_SENSE") (class "Default")
      (node (ref "C10") (pin "2") (pinfunction "2_2") (pintype "passive"))
      (node (ref "D3") (pin "1") (pinfunction "1_1") (pintype "passive"))
      (node (ref "J6") (pin "3") (pinfunction "3_3") (pintype "passive"))
      (node (ref "R14") (pin "2") (pinfunction "2_2") (pintype "passive"))
      (node (ref "R8") (pin "1") (pinfunction "1_1") (pintype "passive"))
    )
    (net (code "3") (name "/C_SENSE") (class "Default")
      (node (ref "C11") (pin "2") (pinfunction "2_2") (pintype "passive"))
      (node (ref "D4") (pin "1") (pinfunction "1_1") (pintype "passive"))
      (node (ref "J6") (pin "4") (pinfunction "4_4") (pintype "passive"))
      (node (ref "R15") (pin "2") (pinfunction "2_2") (pintype "passive"))
      (node (ref "R9") (pin "1") (pinfunction "1_1") (pintype "passive"))
    )
    (net (code "4") (name "/DC_CAL") (class "Default")
      (node (ref "J4") (pin "1") (pinfunction "1_1") (pintype "passive"))
      (node (ref "U1") (pin "12") (pinfunction "DC_CAL_12") (pintype "input"))
    )
    (net (code "5") (name "/EN_GATE") (class "Default")
      (node (ref "J4") (pin "2") (pinfunction "2_2") (pintype "passive"))
      (node (ref "U1") (pin "16") (pinfunction "EN_GATE_16") (pintype "input"))
    )
    (net (code "6") (name "/GH_A") (class "Default")
      (node (ref "R4") (pin "1") (pinfunction "1_1") (pintype "passive"))
      (node (ref "U1") (pin "47") (pinfunction "GH_A_47") (pintype "output"))
    )
    (net (code "7") (name "/GH_B") (class "Default")
      (node (ref "R5") (pin "1") (pinfunction "1_1") (pintype "passive"))
      (node (ref "U1") (pin "42") (pinfunction "GH_B_42") (pintype "output"))
    )
    (net (code "8") (name "/GH_C") (class "Default")
      (node (ref "R6") (pin "1") (pinfunction "1_1") (pintype "passive"))
      (node (ref "U1") (pin "37") (pinfunction "GH_C_37") (pintype "output"))
    )
    (net (code "9") (name "/GL_A") (class "Default")
      (node (ref "R10") (pin "1") (pinfunction "1_1") (pintype "passive"))
      (node (ref "U1") (pin "45") (pinfunction "GL_A_45") (pintype "output"))
    )
    (net (code "10") (name "/GL_B") (class "Default")
      (node (ref "R11") (pin "1") (pinfunction "1_1") (pintype "passive"))
      (node (ref "U1") (pin "40") (pinfunction "GL_B_40") (pintype "output"))
    )
    (net (code "11") (name "/GL_C") (class "Default")
      (node (ref "R12") (pin "1") (pinfunction "1_1") (pintype "passive"))
      (node (ref "U1") (pin "35") (pinfunction "GL_C_35") (pintype "output"))
    )
    (net (code "12") (name "/INH_A") (class "Default")
      (node (ref "J5") (pin "1") (pinfunction "1_1") (pintype "passive"))
      (node (ref "U1") (pin "17") (pinfunction "INH_A_17") (pintype "input"))
    )
    (net (code "13") (name "/INH_B") (class "Default")
      (node (ref "J5") (pin "3") (pinfunction "3_3") (pintype "passive"))
      (node (ref "U1") (pin "19") (pinfunction "INH_B_19") (pintype "input"))
    )
    (net (code "14") (name "/INH_C") (class "Default")
      (node (ref "J5") (pin "5") (pinfunction "5_5") (pintype "passive"))
      (node (ref "U1") (pin "21") (pinfunction "INH_C_21") (pintype "input"))
    )
    (net (code "15") (name "/INL_A") (class "Default")
      (node (ref "J5") (pin "2") (pinfunction "2_2") (pintype "passive"))
      (node (ref "U1") (pin "18") (pinfunction "INL_A_18") (pintype "input"))
    )
    (net (code "16") (name "/INL_B") (class "Default")
      (node (ref "J5") (pin "4") (pinfunction "4_4") (pintype "passive"))
      (node (ref "U1") (pin "20") (pinfunction "INL_B_20") (pintype "input"))
    )
    (net (code "17") (name "/INL_C") (class "Default")
      (node (ref "J5") (pin "6") (pinfunction "6_6") (pintype "passive"))
      (node (ref "U1") (pin "22") (pinfunction "INL_C_22") (pintype "input"))
    )
    (net (code "18") (name "/MotorOutA") (class "Default")
      (node (ref "C22") (pin "1") (pinfunction "1_1") (pintype "passive"))
      (node (ref "J7") (pin "1") (pinfunction "1_1") (pintype "passive"))
      (node (ref "Q") (pin "3") (pinfunction "S_3") (pintype "passive"))
      (node (ref "Q3") (pin "2") (pinfunction "D_2") (pintype "passive"))
      (node (ref "R7") (pin "2") (pinfunction "2_2") (pintype "passive"))
      (node (ref "U1") (pin "46") (pinfunction "SH_A_46") (pintype "input"))
    )
    (net (code "19") (name "/MotorOutB") (class "Default")
      (node (ref "C26") (pin "1") (pinfunction "1_1") (pintype "passive"))
      (node (ref "J7") (pin "2") (pinfunction "2_2") (pintype "passive"))
      (node (ref "Q1") (pin "3") (pinfunction "S_3") (pintype "passive"))
      (node (ref "Q4") (pin "2") (pinfunction "D_2") (pintype "passive"))
      (node (ref "R8") (pin "2") (pinfunction "2_2") (pintype "passive"))
      (node (ref "U1") (pin "41") (pinfunction "SH_B_41") (pintype "input"))
    )
    (net (code "20") (name "/MotorOutC") (class "Default")
      (node (ref "C27") (pin "1") (pinfunction "1_1") (pintype "passive"))
      (node (ref "J7") (pin "3") (pinfunction "3_3") (pintype "passive"))
      (node (ref "Q2") (pin "3") (pinfunction "S_3") (pintype "passive"))
      (node (ref "Q5") (pin "2") (pinfunction "D_2") (pintype "passive"))
      (node (ref "R9") (pin "2") (pinfunction "2_2") (pintype "passive"))
      (node (ref "U1") (pin "36") (pinfunction "SH_C_36") (pintype "input"))
    )
    (net (code "21") (name "/PVDDSENSE") (class "Default")
      (node (ref "C8") (pin "2") (pinfunction "2_2") (pintype "passive"))
      (node (ref "D1") (pin "1") (pinfunction "1_1") (pintype "passive"))
      (node (ref "J6") (pin "1") (pinfunction "1_1") (pintype "passive"))
      (node (ref "R1") (pin "1") (pinfunction "1_1") (pintype "passive"))
      (node (ref "R3") (pin "2") (pinfunction "2_2") (pintype "passive"))
    )
    (net (code "22") (name "/PWRGD") (class "Default")
      (node (ref "J2") (pin "1") (pinfunction "1_1") (pintype "passive"))
      (node (ref "R22") (pin "1") (pinfunction "1_1") (pintype "passive"))
      (node (ref "U1") (pin "4") (pinfunction "PWRGD_4") (pintype "output"))
    )
    (net (code "23") (name "/REF") (class "Default")
      (node (ref "J6") (pin "5") (pinfunction "5_5") (pintype "passive"))
      (node (ref "U1") (pin "24") (pinfunction "REF_24") (pintype "input"))
    )
    (net (code "24") (name "/S1_N") (class "Default")
      (node (ref "C13") (pin "2") (pinfunction "2_2") (pintype "passive"))
      (node (ref "Q3") (pin "3") (pinfunction "S_3") (pintype "passive"))
      (node (ref "R16") (pin "2") (pinfunction "2_2") (pintype "passive"))
      (node (ref "U1") (pin "33") (pinfunction "SN1_33") (pintype "input"))
      (node (ref "U1") (pin "44") (pinfunction "SL_A_44") (pintype "input"))
    )
    (net (code "25") (name "/S2_N") (class "Default")
      (node (ref "C12") (pin "2") (pinfunction "2_2") (pintype "passive"))
      (node (ref "Q4") (pin "3") (pinfunction "S_3") (pintype "passive"))
      (node (ref "R17") (pin "2") (pinfunction "2_2") (pintype "passive"))
      (node (ref "U1") (pin "31") (pinfunction "SN2_31") (pintype "input"))
      (node (ref "U1") (pin "39") (pinfunction "SL_B_39") (pintype "input"))
    )
    (net (code "26") (name "/SO1") (class "Default")
      (node (ref "C31") (pin "2") (pinfunction "2_2") (pintype "passive"))
      (node (ref "J6") (pin "6") (pinfunction "6_6") (pintype "passive"))
      (node (ref "R26") (pin "1") (pinfunction "1_1") (pintype "passive"))
    )
    (net (code "27") (name "/SO2") (class "Default")
      (node (ref "C30") (pin "2") (pinfunction "2_2") (pintype "passive"))
      (node (ref "J6") (pin "7") (pinfunction "7_7") (pintype "passive"))
      (node (ref "R27") (pin "1") (pinfunction "1_1") (pintype "passive"))
    )
    (net (code "28") (name "/SPI_CS") (class "Default")
      (node (ref "J3") (pin "1") (pinfunction "1_1") (pintype "passive"))
      (node (ref "U1") (pin "8") (pinfunction "~{SCS}_8") (pintype "input"))
    )
    (net (code "29") (name "/SPI_SCLK") (class "Default")
      (node (ref "J3") (pin "4") (pinfunction "4_4") (pintype "passive"))
      (node (ref "U1") (pin "11") (pinfunction "SCLK_11") (pintype "input"))
    )
    (net (code "30") (name "/SPI_SDI") (class "Default")
      (node (ref "J3") (pin "2") (pinfunction "2_2") (pintype "passive"))
      (node (ref "U1") (pin "9") (pinfunction "SDI_9") (pintype "input"))
    )
    (net (code "31") (name "/SPI_SDO") (class "Default")
      (node (ref "J3") (pin "3") (pinfunction "3_3") (pintype "passive"))
      (node (ref "U1") (pin "10") (pinfunction "SDO_10") (pintype "output"))
    )
    (net (code "32") (name "/nFAULT") (class "Default")
      (node (ref "J2") (pin "3") (pinfunction "3_3") (pintype "passive"))
      (node (ref "R20") (pin "1") (pinfunction "1_1") (pintype "passive"))
      (node (ref "U1") (pin "6") (pinfunction "~{FAULT}_6") (pintype "output"))
    )
    (net (code "33") (name "/nOCTW") (class "Default")
      (node (ref "J2") (pin "2") (pinfunction "2_2") (pintype "passive"))
      (node (ref "R21") (pin "1") (pinfunction "1_1") (pintype "passive"))
      (node (ref "U1") (pin "5") (pinfunction "~{OCTW}_5") (pintype "output"))
    )
    (net (code "34") (name "GND") (class "Default")
      (node (ref "B1") (pin "3") (pinfunction "3_3") (pintype "passive"))
      (node (ref "C1") (pin "1") (pinfunction "1_1") (pintype "passive"))
      (node (ref "C10") (pin "1") (pinfunction "1_1") (pintype "passive"))
      (node (ref "C11") (pin "1") (pinfunction "1_1") (pintype "passive"))
      (node (ref "C12") (pin "1") (pinfunction "1_1") (pintype "passive"))
      (node (ref "C13") (pin "1") (pinfunction "1_1") (pintype "passive"))
      (node (ref "C14") (pin "2") (pinfunction "2_2") (pintype "passive"))
      (node (ref "C15") (pin "1") (pinfunction "1_1") (pintype "passive"))
      (node (ref "C16") (pin "1") (pinfunction "1_1") (pintype "passive"))
      (node (ref "C17") (pin "2") (pinfunction "2_2") (pintype "passive"))
      (node (ref "C18") (pin "1") (pinfunction "1_1") (pintype "passive"))
      (node (ref "C19") (pin "1") (pinfunction "1_1") (pintype "passive"))
      (node (ref "C2") (pin "1") (pinfunction "1_1") (pintype "passive"))
      (node (ref "C20") (pin "1") (pinfunction "1_1") (pintype "passive"))
      (node (ref "C23") (pin "2") (pinfunction "2_2") (pintype "passive"))
      (node (ref "C24") (pin "1") (pinfunction "1_1") (pintype "passive"))
      (node (ref "C28") (pin "1") (pinfunction "1_1") (pintype "passive"))
      (node (ref "C29") (pin "1") (pinfunction "1_1") (pintype "passive"))
      (node (ref "C3") (pin "1") (pinfunction "1_1") (pintype "passive"))
      (node (ref "C30") (pin "1") (pinfunction "1_1") (pintype "passive"))
      (node (ref "C31") (pin "1") (pinfunction "1_1") (pintype "passive"))
      (node (ref "C32") (pin "1") (pinfunction "1_1") (pintype "passive"))
      (node (ref "C33") (pin "1") (pinfunction "1_1") (pintype "passive"))
      (node (ref "C4") (pin "2") (pinfunction "2_2") (pintype "passive"))
      (node (ref "C5") (pin "2") (pinfunction "2_2") (pintype "passive"))
      (node (ref "C6") (pin "1") (pinfunction "1_1") (pintype "passive"))
      (node (ref "C8") (pin "1") (pinfunction "1_1") (pintype "passive"))
      (node (ref "C9") (pin "1") (pinfunction "1_1") (pintype "passive"))
      (node (ref "D5") (pin "1") (pinfunction "1_1") (pintype "passive"))
      (node (ref "J6") (pin "8") (pinfunction "8_8") (pintype "passive"))
      (node (ref "Q5") (pin "3") (pinfunction "S_3") (pintype "passive"))
      (node (ref "R13") (pin "1") (pinfunction "1_1") (pintype "passive"))
      (node (ref "R14") (pin "1") (pinfunction "1_1") (pintype "passive"))
      (node (ref "R15") (pin "1") (pinfunction "1_1") (pintype "passive"))
      (node (ref "R16") (pin "1") (pinfunction "1_1") (pintype "passive"))
      (node (ref "R17") (pin "1") (pinfunction "1_1") (pintype "passive"))
      (node (ref "R2") (pin "1") (pinfunction "1_1") (pintype "passive"))
      (node (ref "R23") (pin "2") (pinfunction "2_2") (pintype "passive"))
      (node (ref "R24") (pin "1") (pinfunction "1_1") (pintype "passive"))
      (node (ref "R25") (pin "1") (pinfunction "1_1") (pintype "passive"))
      (node (ref "R3") (pin "1") (pinfunction "1_1") (pintype "passive"))
      (node (ref "U1") (pin "28") (pinfunction "AGND_28") (pintype "power_in"))
      (node (ref "U1") (pin "30") (pinfunction "SP2_30") (pintype "input"))
      (node (ref "U1") (pin "32") (pinfunction "SP1_32") (pintype "input"))
      (node (ref "U1") (pin "34") (pinfunction "SL_C_34") (pintype "input"))
      (node (ref "U1") (pin "57") (pinfunction "GND_57") (pintype "power_in"))
    )
    (net (code "35") (name "MAIN_GND") (class "Default")
      (node (ref "B1") (pin "4") (pinfunction "4_4") (pintype "passive"))
      (node (ref "J1") (pin "2") (pinfunction "2_2") (pintype "passive"))
    )
    (net (code "36") (name "MAIN_POWER") (class "Default")
      (node (ref "B1") (pin "1") (pinfunction "1_1") (pintype "passive"))
      (node (ref "J1") (pin "1") (pinfunction "1_1") (pintype "passive"))
    )
    (net (code "37") (name "Net-(C7-Pad1)") (class "Default")
      (node (ref "C7") (pin "1") (pinfunction "1_1") (pintype "passive"))
      (node (ref "R2") (pin "2") (pinfunction "2_2") (pintype "passive"))
    )
    (net (code "38") (name "Net-(C18-Pad2)") (class "Default")
      (node (ref "C18") (pin "2") (pinfunction "2_2") (pintype "passive"))
      (node (ref "R18") (pin "1") (pinfunction "1_1") (pintype "passive"))
    )
    (net (code "39") (name "Net-(C21-Pad1)") (class "Default")
      (node (ref "C21") (pin "1") (pinfunction "1_1") (pintype "passive"))
      (node (ref "D5") (pin "2") (pinfunction "2_2") (pintype "passive"))
      (node (ref "L1") (pin "1") (pinfunction "1_1") (pintype "passive"))
      (node (ref "U1") (pin "50") (pinfunction "PH_50") (pintype "output"))
      (node (ref "U1") (pin "51") (pinfunction "PH_51") (pintype "output"))
    )
    (net (code "40") (name "Net-(Q-G)") (class "Default")
      (node (ref "Q") (pin "1") (pinfunction "G_1") (pintype "passive"))
      (node (ref "R4") (pin "2") (pinfunction "2_2") (pintype "passive"))
    )
    (net (code "41") (name "Net-(Q1-G)") (class "Default")
      (node (ref "Q1") (pin "1") (pinfunction "G_1") (pintype "passive"))
      (node (ref "R5") (pin "2") (pinfunction "2_2") (pintype "passive"))
    )
    (net (code "42") (name "Net-(Q2-G)") (class "Default")
      (node (ref "Q2") (pin "1") (pinfunction "G_1") (pintype "passive"))
      (node (ref "R6") (pin "2") (pinfunction "2_2") (pintype "passive"))
    )
    (net (code "43") (name "Net-(Q3-G)") (class "Default")
      (node (ref "Q3") (pin "1") (pinfunction "G_1") (pintype "passive"))
      (node (ref "R10") (pin "2") (pinfunction "2_2") (pintype "passive"))
    )
    (net (code "44") (name "Net-(Q4-G)") (class "Default")
      (node (ref "Q4") (pin "1") (pinfunction "G_1") (pintype "passive"))
      (node (ref "R11") (pin "2") (pinfunction "2_2") (pintype "passive"))
    )
    (net (code "45") (name "Net-(Q5-G)") (class "Default")
      (node (ref "Q5") (pin "1") (pinfunction "G_1") (pintype "passive"))
      (node (ref "R12") (pin "2") (pinfunction "2_2") (pintype "passive"))
    )
    (net (code "46") (name "Net-(U1-AVDD)") (class "Default")
      (node (ref "C29") (pin "2") (pinfunction "2_2") (pintype "passive"))
      (node (ref "U1") (pin "27") (pinfunction "AVDD_27") (pintype "power_in"))
    )
    (net (code "47") (name "Net-(U1-BST_A)") (class "Default")
      (node (ref "C22") (pin "2") (pinfunction "2_2") (pintype "passive"))
      (node (ref "U1") (pin "48") (pinfunction "BST_A_48") (pintype "power_in"))
    )
    (net (code "48") (name "Net-(U1-BST_B)") (class "Default")
      (node (ref "C26") (pin "2") (pinfunction "2_2") (pintype "passive"))
      (node (ref "U1") (pin "43") (pinfunction "BST_B_43") (pintype "power_in"))
    )
    (net (code "49") (name "Net-(U1-BST_BK)") (class "Default")
      (node (ref "C21") (pin "2") (pinfunction "2_2") (pintype "passive"))
      (node (ref "U1") (pin "52") (pinfunction "BST_BK_52") (pintype "power_in"))
    )
    (net (code "50") (name "Net-(U1-BST_C)") (class "Default")
      (node (ref "C27") (pin "2") (pinfunction "2_2") (pintype "passive"))
      (node (ref "U1") (pin "38") (pinfunction "BST_C_38") (pintype "power_in"))
    )
    (net (code "51") (name "Net-(U1-COMP)") (class "Default")
      (node (ref "C16") (pin "2") (pinfunction "2_2") (pintype "passive"))
      (node (ref "R18") (pin "2") (pinfunction "2_2") (pintype "passive"))
      (node (ref "U1") (pin "2") (pinfunction "COMP_2") (pintype "output"))
    )
    (net (code "52") (name "Net-(U1-CP1)") (class "Default")
      (node (ref "C25") (pin "2") (pinfunction "2_2") (pintype "passive"))
      (node (ref "U1") (pin "14") (pinfunction "CP1_14") (pintype "power_in"))
    )
    (net (code "53") (name "Net-(U1-CP2)") (class "Default")
      (node (ref "C25") (pin "1") (pinfunction "1_1") (pintype "passive"))
      (node (ref "U1") (pin "15") (pinfunction "CP2_15") (pintype "power_in"))
    )
    (net (code "54") (name "Net-(U1-DTC)") (class "Default")
      (node (ref "R25") (pin "2") (pinfunction "2_2") (pintype "passive"))
      (node (ref "U1") (pin "7") (pinfunction "DTC_7") (pintype "input"))
    )
    (net (code "55") (name "Net-(U1-DVDD)") (class "Default")
      (node (ref "C28") (pin "2") (pinfunction "2_2") (pintype "passive"))
      (node (ref "U1") (pin "23") (pinfunction "DVDD_23") (pintype "power_in"))
    )
    (net (code "56") (name "Net-(U1-GVDD)") (class "Default")
      (node (ref "C24") (pin "2") (pinfunction "2_2") (pintype "passive"))
      (node (ref "U1") (pin "13") (pinfunction "GVDD_13") (pintype "power_in"))
    )
    (net (code "57") (name "Net-(U1-RT_CLK)") (class "Default")
      (node (ref "R23") (pin "1") (pinfunction "1_1") (pintype "passive"))
      (node (ref "U1") (pin "1") (pinfunction "RT_CLK_1") (pintype "input"))
    )
    (net (code "58") (name "Net-(U1-SO1)") (class "Default")
      (node (ref "R26") (pin "2") (pinfunction "2_2") (pintype "passive"))
      (node (ref "U1") (pin "25") (pinfunction "SO1_25") (pintype "output"))
    )
    (net (code "59") (name "Net-(U1-SO2)") (class "Default")
      (node (ref "R27") (pin "2") (pinfunction "2_2") (pintype "passive"))
      (node (ref "U1") (pin "26") (pinfunction "SO2_26") (pintype "output"))
    )
    (net (code "60") (name "Net-(U1-SS_TR)") (class "Default")
      (node (ref "C17") (pin "1") (pinfunction "1_1") (pintype "passive"))
      (node (ref "U1") (pin "56") (pinfunction "SS_TR_56") (pintype "input"))
    )
    (net (code "61") (name "Net-(U1-VSENSE)") (class "Default")
      (node (ref "R19") (pin "1") (pinfunction "1_1") (pintype "passive"))
      (node (ref "R24") (pin "2") (pinfunction "2_2") (pintype "passive"))
      (node (ref "U1") (pin "3") (pinfunction "VSENSE_3") (pintype "input"))
    )
    (net (code "62") (name "PVDD") (class "Default")
      (node (ref "B1") (pin "2") (pinfunction "2_2") (pintype "passive"))
      (node (ref "C1") (pin "2") (pinfunction "2_2") (pintype "passive"))
      (node (ref "C14") (pin "1") (pinfunction "1_1") (pintype "passive"))
      (node (ref "C15") (pin "2") (pinfunction "2_2") (pintype "passive"))
      (node (ref "C19") (pin "2") (pinfunction "2_2") (pintype "passive"))
      (node (ref "C2") (pin "2") (pinfunction "2_2") (pintype "passive"))
      (node (ref "C20") (pin "2") (pinfunction "2_2") (pintype "passive"))
      (node (ref "C3") (pin "2") (pinfunction "2_2") (pintype "passive"))
      (node (ref "C32") (pin "2") (pinfunction "2_2") (pintype "passive"))
      (node (ref "C33") (pin "2") (pinfunction "2_2") (pintype "passive"))
      (node (ref "C4") (pin "1") (pinfunction "1_1") (pintype "passive"))
      (node (ref "C5") (pin "1") (pinfunction "1_1") (pintype "passive"))
      (node (ref "C6") (pin "2") (pinfunction "2_2") (pintype "passive"))
      (node (ref "C7") (pin "2") (pinfunction "2_2") (pintype "passive"))
      (node (ref "Q") (pin "2") (pinfunction "D_2") (pintype "passive"))
      (node (ref "Q1") (pin "2") (pinfunction "D_2") (pintype "passive"))
      (node (ref "Q2") (pin "2") (pinfunction "D_2") (pintype "passive"))
      (node (ref "R1") (pin "2") (pinfunction "2_2") (pintype "passive"))
      (node (ref "U1") (pin "29") (pinfunction "PVDD1_29") (pintype "power_in"))
      (node (ref "U1") (pin "53") (pinfunction "PVDD2_53") (pintype "power_in"))
      (node (ref "U1") (pin "54") (pinfunction "PVDD2_54") (pintype "power_in"))
    )
    (net (code "63") (name "VCC") (class "Default")
      (node (ref "C23") (pin "1") (pinfunction "1_1") (pintype "passive"))
      (node (ref "D1") (pin "2") (pinfunction "2_2") (pintype "passive"))
      (node (ref "D2") (pin "2") (pinfunction "2_2") (pintype "passive"))
      (node (ref "D3") (pin "2") (pinfunction "2_2") (pintype "passive"))
      (node (ref "D4") (pin "2") (pinfunction "2_2") (pintype "passive"))
      (node (ref "L1") (pin "2") (pinfunction "2_2") (pintype "passive"))
      (node (ref "R19") (pin "2") (pinfunction "2_2") (pintype "passive"))
      (node (ref "R20") (pin "2") (pinfunction "2_2") (pintype "passive"))
      (node (ref "R21") (pin "2") (pinfunction "2_2") (pintype "passive"))
      (node (ref "R22") (pin "2") (pinfunction "2_2") (pintype "passive"))
      (node (ref "U1") (pin "49") (pinfunction "VDD_SPI_49") (pintype "input"))
    )
    (net (code "64") (name "unconnected-(U1-EN_BUCK-Pad55)") (class "Default")
      (node (ref "U1") (pin "55") (pinfunction "EN_BUCK_55") (pintype "input+no_connect"))
    )
  )
)
